# PMW3360-breakout_02_v11.net
KiCad netlist of a schematic drawn in EAGLE
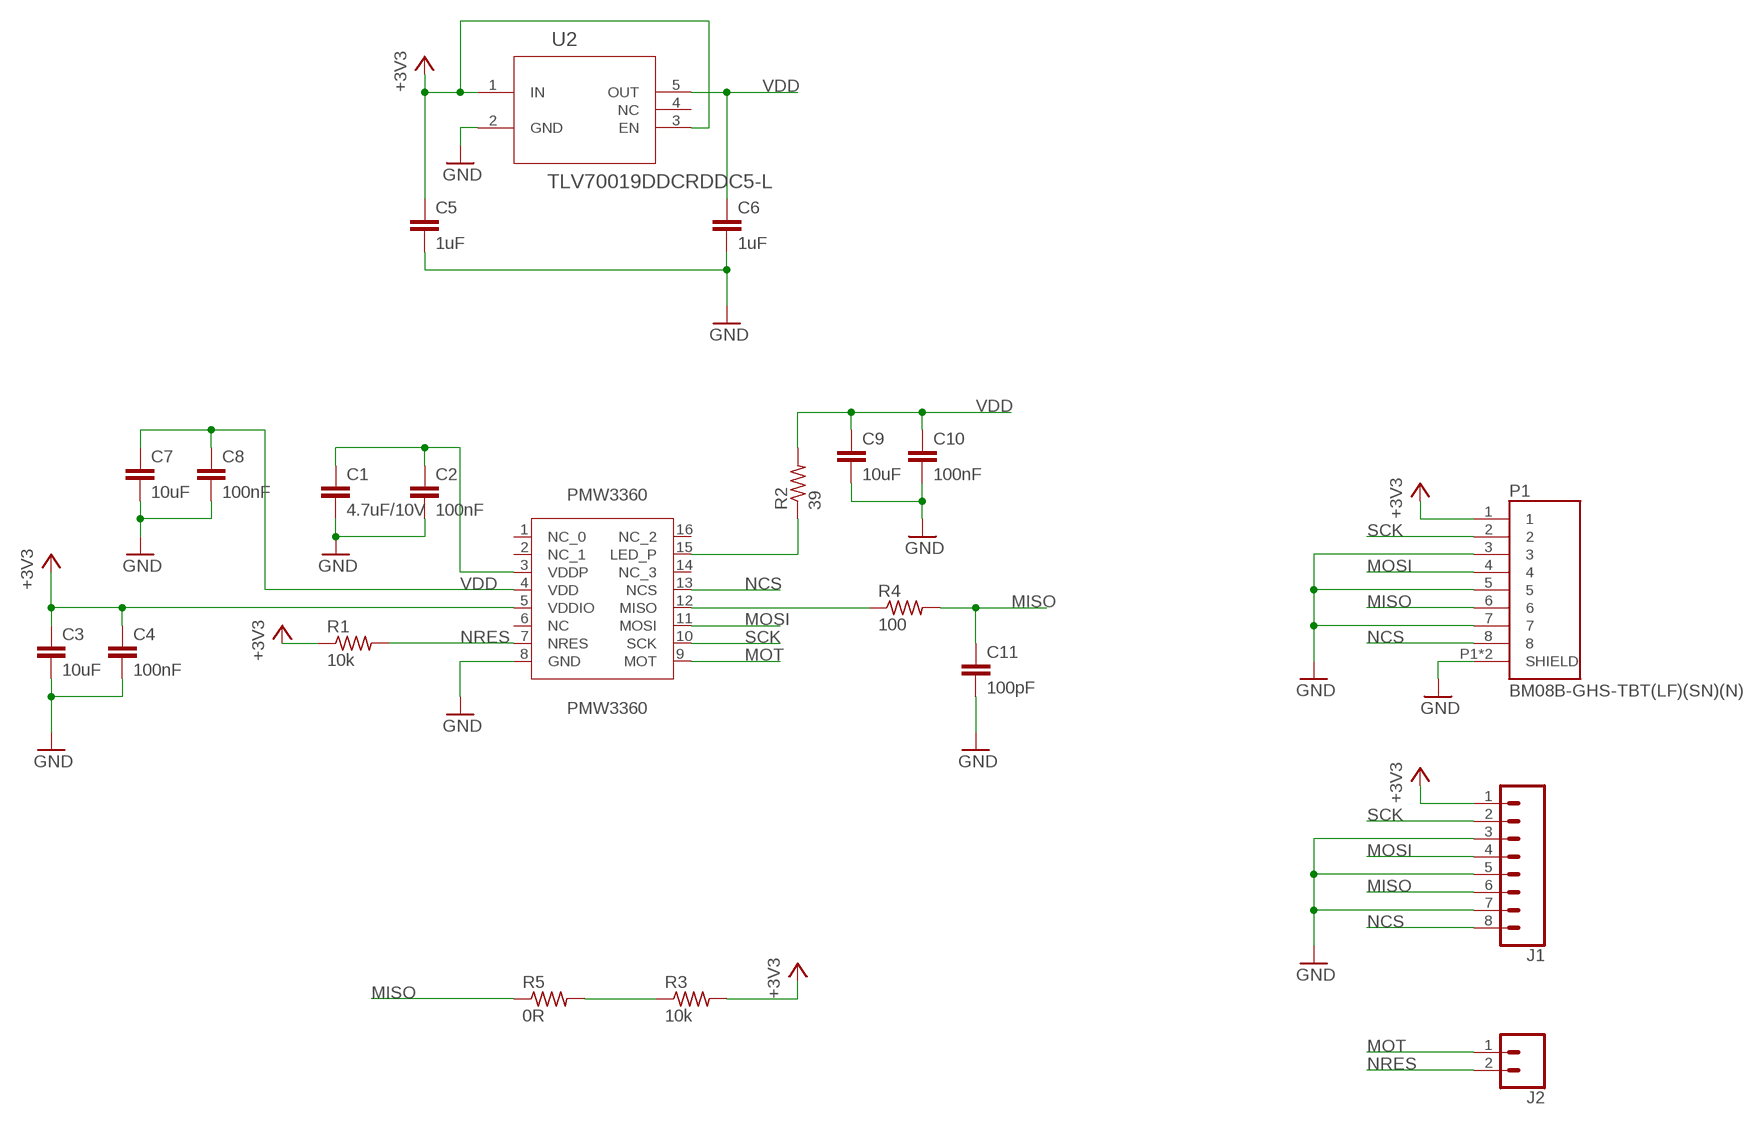
[diagram p0: schematic, sheet 1]

(export (version "E")
  (design (tool "Eeschema 10.0.6"))
  (components
    (comp (ref "C1")
      (value "4.7uF/10V")
      (footprint "eagle-import:C0603")
      (libsource (lib "eagle-import") (part "C-EUC0603"))
    )
    (comp (ref "C2")
      (value "100nF")
      (footprint "eagle-import:C0402")
      (libsource (lib "eagle-import") (part "C-EUC0402"))
    )
    (comp (ref "C3")
      (value "10uF")
      (footprint "eagle-import:C0402")
      (libsource (lib "eagle-import") (part "C-EUC0402"))
    )
    (comp (ref "C4")
      (value "100nF")
      (footprint "eagle-import:C0402")
      (libsource (lib "eagle-import") (part "C-EUC0402"))
    )
    (comp (ref "C5")
      (value "1uF")
      (footprint "eagle-import:C0402")
      (libsource (lib "eagle-import") (part "C-EUC0402"))
    )
    (comp (ref "C6")
      (value "1uF")
      (footprint "eagle-import:C0402")
      (libsource (lib "eagle-import") (part "C-EUC0402"))
    )
    (comp (ref "C7")
      (value "10uF")
      (footprint "eagle-import:C0402")
      (libsource (lib "eagle-import") (part "C-EUC0402"))
    )
    (comp (ref "C8")
      (value "100nF")
      (footprint "eagle-import:C0402")
      (libsource (lib "eagle-import") (part "C-EUC0402"))
    )
    (comp (ref "C9")
      (value "10uF")
      (footprint "eagle-import:C0402")
      (libsource (lib "eagle-import") (part "C-EUC0402"))
    )
    (comp (ref "C10")
      (value "100nF")
      (footprint "eagle-import:C0402")
      (libsource (lib "eagle-import") (part "C-EUC0402"))
    )
    (comp (ref "C11")
      (value "100pF")
      (footprint "eagle-import:C0402K")
      (libsource (lib "eagle-import") (part "C-EUC0402K"))
    )
    (comp (ref "J1")
      (value "CONN_08\"")
      (footprint "eagle-import:1X08")
      (libsource (lib "eagle-import") (part "CONN_08{dblquote}"))
    )
    (comp (ref "J2")
      (value "CONN_02")
      (footprint "eagle-import:1X02")
      (libsource (lib "eagle-import") (part "CONN_02"))
    )
    (comp (ref "P1")
      (value "BM08B-GHS-TBT(LF)(SN)(N)")
      (footprint "eagle-import:JST_BM08B-GHS-TBT(LF)(SN)(N)")
      (fields (field (name "MF") "JST Sales"))
      (libsource (lib "eagle-import") (part "BM08B-GHS-TBT(LF)(SN)(N)"))
    )
    (comp (ref "PMW3360")
      (value "PMW3360")
      (footprint "eagle-import:PMW3360")
      (libsource (lib "eagle-import") (part "PMW3360"))
    )
    (comp (ref "R1")
      (value "10k")
      (footprint "eagle-import:R0402")
      (libsource (lib "eagle-import") (part "R-US_R0402"))
    )
    (comp (ref "R2")
      (value "39")
      (footprint "eagle-import:R0402")
      (libsource (lib "eagle-import") (part "R-US_R0402"))
    )
    (comp (ref "R3")
      (value "10k")
      (footprint "eagle-import:R0402")
      (libsource (lib "eagle-import") (part "R-US_R0402"))
    )
    (comp (ref "R4")
      (value "100")
      (footprint "eagle-import:R0402")
      (libsource (lib "eagle-import") (part "R-US_R0402"))
    )
    (comp (ref "R5")
      (value "0R")
      (footprint "eagle-import:R0402")
      (libsource (lib "eagle-import") (part "R-US_R0402"))
    )
    (comp (ref "U2")
      (value "TLV70019DDCRDDC5-L")
      (footprint "eagle-import:DDC5-L")
      (fields
        (field (name "MANUFACTURER_PART_NUMBER") "TLV70019DDCR")
        (field (name "COPYRIGHT") "Copyright (C) 2024 Ultra Librarian. All rights reserved.")
      )
      (libsource (lib "eagle-import") (part "TLV70019DDCRDDC5-L"))
    )
  )
  (nets
    (net (code "1") (name "+3V3") (class "Default")
      (node (ref "C3") (pin "1") (pinfunction "1_1") (pintype "passive"))
      (node (ref "C4") (pin "1") (pinfunction "1_1") (pintype "passive"))
      (node (ref "C5") (pin "1") (pinfunction "1_1") (pintype "passive"))
      (node (ref "J1") (pin "1") (pinfunction "1_1") (pintype "passive"))
      (node (ref "P1") (pin "1") (pinfunction "1_1") (pintype "passive"))
      (node (ref "PMW3360") (pin "5") (pinfunction "VDDIO_5") (pintype "power_in"))
      (node (ref "R1") (pin "1") (pinfunction "1_1") (pintype "passive"))
      (node (ref "R3") (pin "2") (pinfunction "2_2") (pintype "passive"))
      (node (ref "U2") (pin "1") (pinfunction "IN_1") (pintype "input"))
      (node (ref "U2") (pin "3") (pinfunction "EN_3") (pintype "passive"))
    )
    (net (code "2") (name "/MISO") (class "Default")
      (node (ref "C11") (pin "1") (pinfunction "1_1") (pintype "passive"))
      (node (ref "J1") (pin "6") (pinfunction "6_6") (pintype "passive"))
      (node (ref "P1") (pin "6") (pinfunction "6_6") (pintype "passive"))
      (node (ref "R4") (pin "2") (pinfunction "2_2") (pintype "passive"))
      (node (ref "R5") (pin "1") (pinfunction "1_1") (pintype "passive"))
    )
    (net (code "3") (name "/MOSI") (class "Default")
      (node (ref "J1") (pin "4") (pinfunction "4_4") (pintype "passive"))
      (node (ref "P1") (pin "4") (pinfunction "4_4") (pintype "passive"))
      (node (ref "PMW3360") (pin "11") (pinfunction "MOSI_11") (pintype "input"))
    )
    (net (code "4") (name "/MOT") (class "Default")
      (node (ref "J2") (pin "1") (pinfunction "1_1") (pintype "passive"))
      (node (ref "PMW3360") (pin "9") (pinfunction "MOT_9") (pintype "output"))
    )
    (net (code "5") (name "/NCS") (class "Default")
      (node (ref "J1") (pin "8") (pinfunction "8_8") (pintype "passive"))
      (node (ref "P1") (pin "8") (pinfunction "8_8") (pintype "passive"))
      (node (ref "PMW3360") (pin "13") (pinfunction "NCS_13") (pintype "input"))
    )
    (net (code "6") (name "/NRES") (class "Default")
      (node (ref "J2") (pin "2") (pinfunction "2_2") (pintype "passive"))
      (node (ref "PMW3360") (pin "7") (pinfunction "NRES_7") (pintype "input"))
      (node (ref "R1") (pin "2") (pinfunction "2_2") (pintype "passive"))
    )
    (net (code "7") (name "/SCK") (class "Default")
      (node (ref "J1") (pin "2") (pinfunction "2_2") (pintype "passive"))
      (node (ref "P1") (pin "2") (pinfunction "2_2") (pintype "passive"))
      (node (ref "PMW3360") (pin "10") (pinfunction "SCK_10") (pintype "input"))
    )
    (net (code "8") (name "/VDD") (class "Default")
      (node (ref "C10") (pin "1") (pinfunction "1_1") (pintype "passive"))
      (node (ref "C6") (pin "1") (pinfunction "1_1") (pintype "passive"))
      (node (ref "C7") (pin "1") (pinfunction "1_1") (pintype "passive"))
      (node (ref "C8") (pin "1") (pinfunction "1_1") (pintype "passive"))
      (node (ref "C9") (pin "1") (pinfunction "1_1") (pintype "passive"))
      (node (ref "PMW3360") (pin "4") (pinfunction "VDD_4") (pintype "power_in"))
      (node (ref "R2") (pin "2") (pinfunction "2_2") (pintype "passive"))
      (node (ref "U2") (pin "5") (pinfunction "OUT_5") (pintype "output"))
    )
    (net (code "9") (name "GND") (class "Default")
      (node (ref "C1") (pin "2") (pinfunction "2_2") (pintype "passive"))
      (node (ref "C10") (pin "2") (pinfunction "2_2") (pintype "passive"))
      (node (ref "C11") (pin "2") (pinfunction "2_2") (pintype "passive"))
      (node (ref "C2") (pin "2") (pinfunction "2_2") (pintype "passive"))
      (node (ref "C3") (pin "2") (pinfunction "2_2") (pintype "passive"))
      (node (ref "C4") (pin "2") (pinfunction "2_2") (pintype "passive"))
      (node (ref "C5") (pin "2") (pinfunction "2_2") (pintype "passive"))
      (node (ref "C6") (pin "2") (pinfunction "2_2") (pintype "passive"))
      (node (ref "C7") (pin "2") (pinfunction "2_2") (pintype "passive"))
      (node (ref "C8") (pin "2") (pinfunction "2_2") (pintype "passive"))
      (node (ref "C9") (pin "2") (pinfunction "2_2") (pintype "passive"))
      (node (ref "J1") (pin "3") (pinfunction "3_3") (pintype "passive"))
      (node (ref "J1") (pin "5") (pinfunction "5_5") (pintype "passive"))
      (node (ref "J1") (pin "7") (pinfunction "7_7") (pintype "passive"))
      (node (ref "P1") (pin "3") (pinfunction "3_3") (pintype "passive"))
      (node (ref "P1") (pin "5") (pinfunction "5_5") (pintype "passive"))
      (node (ref "P1") (pin "7") (pinfunction "7_7") (pintype "passive"))
      (node (ref "P1") (pin "P1") (pinfunction "SHIELD_P1") (pintype "passive"))
      (node (ref "P1") (pin "P2") (pinfunction "SHIELD_P2") (pintype "passive"))
      (node (ref "PMW3360") (pin "8") (pinfunction "GND_8") (pintype "power_in"))
      (node (ref "U2") (pin "2") (pinfunction "GND_2") (pintype "power_in"))
    )
    (net (code "10") (name "Net-(PMW3360-LED_P)") (class "Default")
      (node (ref "PMW3360") (pin "15") (pinfunction "LED_P_15") (pintype "input"))
      (node (ref "R2") (pin "1") (pinfunction "1_1") (pintype "passive"))
    )
    (net (code "11") (name "Net-(PMW3360-MISO)") (class "Default")
      (node (ref "PMW3360") (pin "12") (pinfunction "MISO_12") (pintype "output"))
      (node (ref "R4") (pin "1") (pinfunction "1_1") (pintype "passive"))
    )
    (net (code "12") (name "Net-(PMW3360-VDDP)") (class "Default")
      (node (ref "C1") (pin "1") (pinfunction "1_1") (pintype "passive"))
      (node (ref "C2") (pin "1") (pinfunction "1_1") (pintype "passive"))
      (node (ref "PMW3360") (pin "3") (pinfunction "VDDP_3") (pintype "power_in"))
    )
    (net (code "13") (name "Net-(R3-Pad1)") (class "Default")
      (node (ref "R3") (pin "1") (pinfunction "1_1") (pintype "passive"))
      (node (ref "R5") (pin "2") (pinfunction "2_2") (pintype "passive"))
    )
    (net (code "14") (name "unconnected-(PMW3360-NC-Pad6)") (class "Default")
      (node (ref "PMW3360") (pin "6") (pinfunction "NC_6") (pintype "no_connect"))
    )
    (net (code "15") (name "unconnected-(PMW3360-NC_0-Pad1)") (class "Default")
      (node (ref "PMW3360") (pin "1") (pinfunction "NC_0_1") (pintype "no_connect"))
    )
    (net (code "16") (name "unconnected-(PMW3360-NC_1-Pad2)") (class "Default")
      (node (ref "PMW3360") (pin "2") (pinfunction "NC_1_2") (pintype "no_connect"))
    )
    (net (code "17") (name "unconnected-(PMW3360-NC_2-Pad16)") (class "Default")
      (node (ref "PMW3360") (pin "16") (pinfunction "NC_2_16") (pintype "no_connect"))
    )
    (net (code "18") (name "unconnected-(PMW3360-NC_3-Pad14)") (class "Default")
      (node (ref "PMW3360") (pin "14") (pinfunction "NC_3_14") (pintype "no_connect"))
    )
    (net (code "19") (name "unconnected-(U2-NC-Pad4)") (class "Default")
      (node (ref "U2") (pin "4") (pinfunction "NC_4") (pintype "passive"))
    )
  )
)
